# MP2307.net
KiCad netlist of a schematic drawn in EAGLE
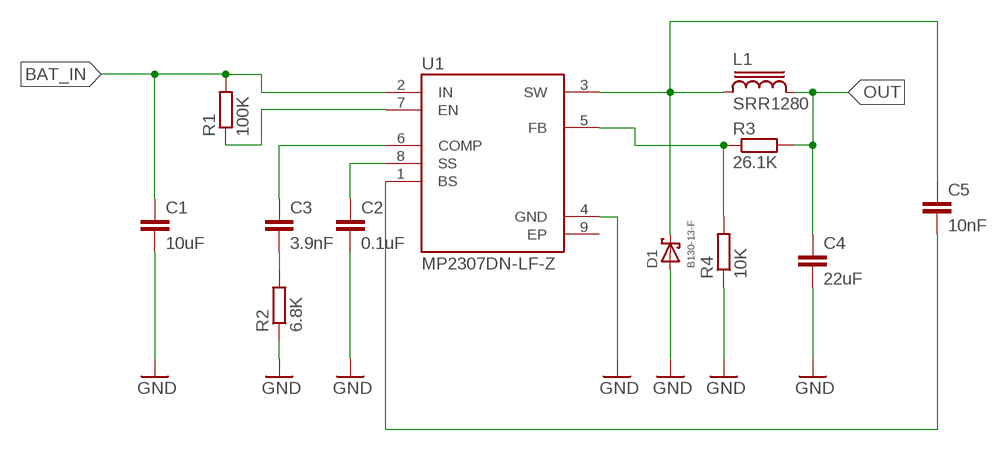
[diagram p0: schematic, sheet 1]

(export (version "E")
  (design (tool "Eeschema 10.0.6"))
  (components
    (comp (ref "C1")
      (value "10uF")
      (footprint "eagle-import:C0805")
      (libsource (lib "eagle-import") (part "C-EUC0805"))
    )
    (comp (ref "C2")
      (value "0.1uF")
      (footprint "eagle-import:C0805")
      (libsource (lib "eagle-import") (part "C-EUC0805"))
    )
    (comp (ref "C3")
      (value "3.9nF")
      (footprint "eagle-import:C0805")
      (libsource (lib "eagle-import") (part "C-EUC0805"))
    )
    (comp (ref "C4")
      (value "22uF")
      (footprint "eagle-import:C0805")
      (libsource (lib "eagle-import") (part "C-EUC0805"))
    )
    (comp (ref "C5")
      (value "10nF")
      (footprint "eagle-import:C0805")
      (libsource (lib "eagle-import") (part "C-EUC0805"))
    )
    (comp (ref "D1")
      (value "B130-13-F")
      (footprint "eagle-import:SMA")
      (fields (field (name "MF") "Multicomp"))
      (libsource (lib "eagle-import") (part "B130-13-F"))
    )
    (comp (ref "L1")
      (value "SRR1280")
      (footprint "eagle-import:SRR1280")
      (libsource (lib "eagle-import") (part "SRR1280"))
    )
    (comp (ref "R1")
      (value "100K")
      (footprint "eagle-import:R0805")
      (libsource (lib "eagle-import") (part "R-EU_R0805"))
    )
    (comp (ref "R2")
      (value "6.8K")
      (footprint "eagle-import:R0805")
      (libsource (lib "eagle-import") (part "R-EU_R0805"))
    )
    (comp (ref "R3")
      (value "26.1K")
      (footprint "eagle-import:R0805")
      (libsource (lib "eagle-import") (part "R-EU_R0805"))
    )
    (comp (ref "R4")
      (value "10K")
      (footprint "eagle-import:R0805")
      (libsource (lib "eagle-import") (part "R-EU_R0805"))
    )
    (comp (ref "U1")
      (value "MP2307DN-LF-Z")
      (footprint "eagle-import:SOIC127P600X170-9N")
      (fields (field (name "MF") "Monolithic Power"))
      (libsource (lib "eagle-import") (part "MP2307DN-LF-Z"))
    )
  )
  (nets
    (net (code "1") (name "/EP") (class "Default")
      (node (ref "U1") (pin "9") (pinfunction "EP_9") (pintype "power_in"))
    )
    (net (code "2") (name "BAT_IN") (class "Default")
      (node (ref "C1") (pin "1") (pinfunction "1_1") (pintype "passive"))
      (node (ref "R1") (pin "2") (pinfunction "2_2") (pintype "passive"))
      (node (ref "U1") (pin "2") (pinfunction "IN_2") (pintype "input"))
    )
    (net (code "3") (name "GND") (class "Default")
      (node (ref "C1") (pin "2") (pinfunction "2_2") (pintype "passive"))
      (node (ref "C2") (pin "2") (pinfunction "2_2") (pintype "passive"))
      (node (ref "C4") (pin "2") (pinfunction "2_2") (pintype "passive"))
      (node (ref "D1") (pin "A") (pinfunction "A_A") (pintype "passive"))
      (node (ref "R2") (pin "1") (pinfunction "1_1") (pintype "passive"))
      (node (ref "R4") (pin "1") (pinfunction "1_1") (pintype "passive"))
      (node (ref "U1") (pin "4") (pinfunction "GND_4") (pintype "power_in"))
    )
    (net (code "4") (name "Net-(C3-Pad2)") (class "Default")
      (node (ref "C3") (pin "2") (pinfunction "2_2") (pintype "passive"))
      (node (ref "R2") (pin "2") (pinfunction "2_2") (pintype "passive"))
    )
    (net (code "5") (name "Net-(U1-BS)") (class "Default")
      (node (ref "C5") (pin "2") (pinfunction "2_2") (pintype "passive"))
      (node (ref "U1") (pin "1") (pinfunction "BS_1") (pintype "passive"))
    )
    (net (code "6") (name "Net-(U1-COMP)") (class "Default")
      (node (ref "C3") (pin "1") (pinfunction "1_1") (pintype "passive"))
      (node (ref "U1") (pin "6") (pinfunction "COMP_6") (pintype "passive"))
    )
    (net (code "7") (name "Net-(U1-EN)") (class "Default")
      (node (ref "R1") (pin "1") (pinfunction "1_1") (pintype "passive"))
      (node (ref "U1") (pin "7") (pinfunction "EN_7") (pintype "input"))
    )
    (net (code "8") (name "Net-(U1-FB)") (class "Default")
      (node (ref "R3") (pin "1") (pinfunction "1_1") (pintype "passive"))
      (node (ref "R4") (pin "2") (pinfunction "2_2") (pintype "passive"))
      (node (ref "U1") (pin "5") (pinfunction "FB_5") (pintype "input"))
    )
    (net (code "9") (name "Net-(U1-SS)") (class "Default")
      (node (ref "C2") (pin "1") (pinfunction "1_1") (pintype "passive"))
      (node (ref "U1") (pin "8") (pinfunction "SS_8") (pintype "passive"))
    )
    (net (code "10") (name "Net-(U1-SW)") (class "Default")
      (node (ref "C5") (pin "1") (pinfunction "1_1") (pintype "passive"))
      (node (ref "D1") (pin "C") (pinfunction "C_C") (pintype "passive"))
      (node (ref "L1") (pin "1") (pinfunction "1_1") (pintype "passive"))
      (node (ref "U1") (pin "3") (pinfunction "SW_3") (pintype "output"))
    )
    (net (code "11") (name "OUT") (class "Default")
      (node (ref "C4") (pin "1") (pinfunction "1_1") (pintype "passive"))
      (node (ref "L1") (pin "2") (pinfunction "2_2") (pintype "passive"))
      (node (ref "R3") (pin "2") (pinfunction "2_2") (pintype "passive"))
    )
  )
)
